# Player_Module.net
KiCad netlist of a schematic drawn in EAGLE
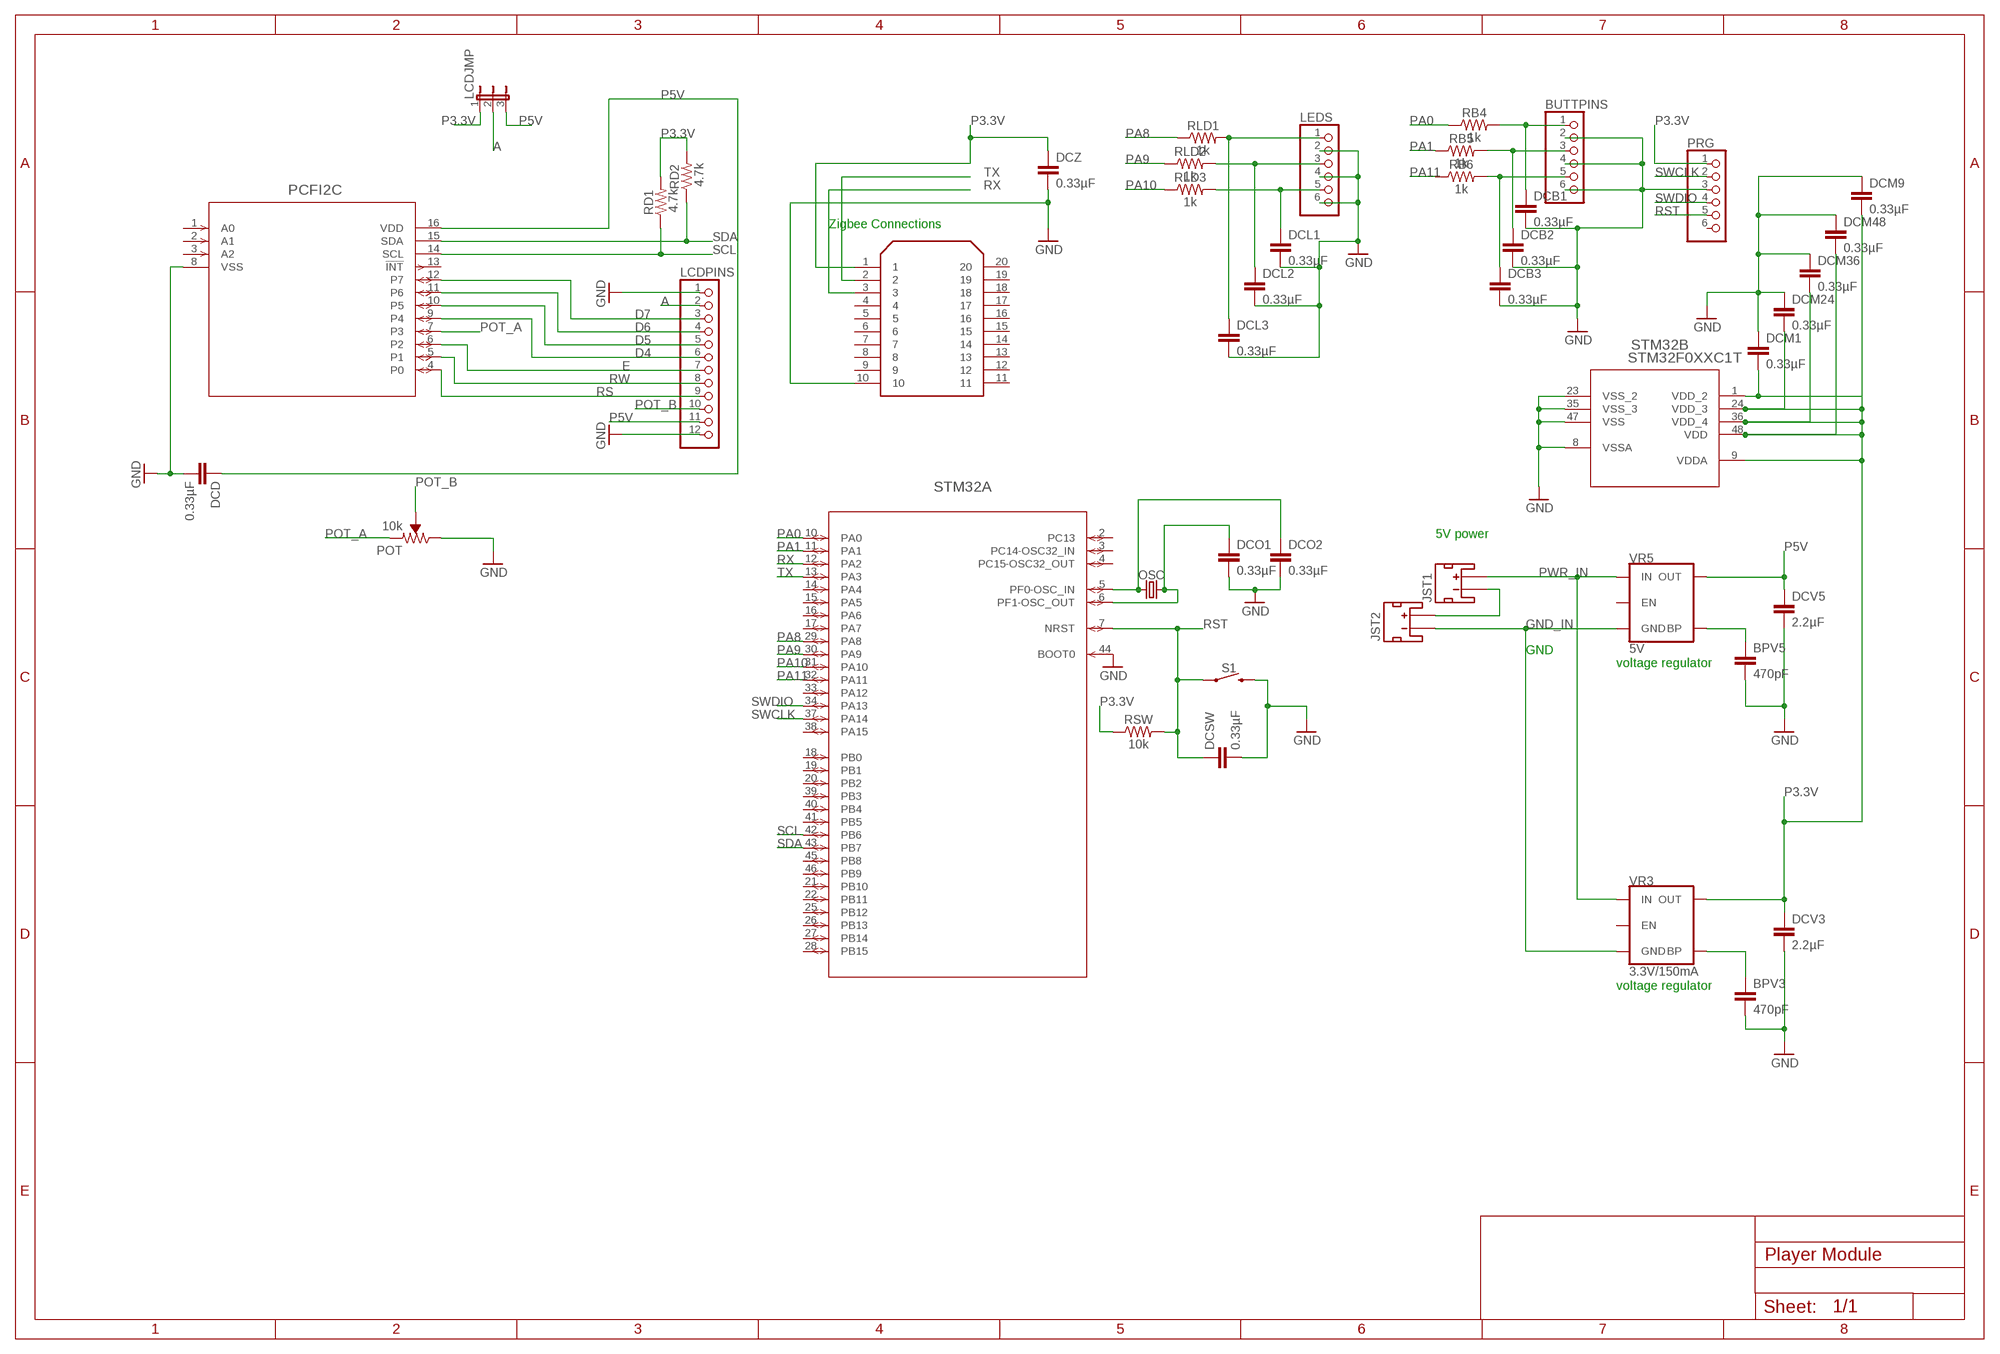
[diagram p0: schematic, sheet 1]

(export (version "E")
  (design (tool "Eeschema 10.0.6"))
  (components
    (comp (ref "BPV3")
      (value "470pF")
      (footprint "eagle-import:0805")
      (libsource (lib "eagle-import") (part "0.33UF/330NF-0805-50V-10%"))
    )
    (comp (ref "BPV5")
      (value "470pF")
      (footprint "eagle-import:0805")
      (libsource (lib "eagle-import") (part "0.33UF/330NF-0805-50V-10%"))
    )
    (comp (ref "BUTTPINS")
      (value "PINHD-1X6")
      (footprint "eagle-import:1X06")
      (libsource (lib "eagle-import") (part "PINHD-1X6"))
    )
    (comp (ref "DCB1")
      (value "0.33µF")
      (footprint "eagle-import:0805")
      (libsource (lib "eagle-import") (part "0.33UF/330NF-0805-50V-10%"))
    )
    (comp (ref "DCB2")
      (value "0.33µF")
      (footprint "eagle-import:0805")
      (libsource (lib "eagle-import") (part "0.33UF/330NF-0805-50V-10%"))
    )
    (comp (ref "DCB3")
      (value "0.33µF")
      (footprint "eagle-import:0805")
      (libsource (lib "eagle-import") (part "0.33UF/330NF-0805-50V-10%"))
    )
    (comp (ref "DCD")
      (value "0.33µF")
      (footprint "eagle-import:0805")
      (libsource (lib "eagle-import") (part "0.33UF/330NF-0805-50V-10%"))
    )
    (comp (ref "DCL1")
      (value "0.33µF")
      (footprint "eagle-import:0805")
      (libsource (lib "eagle-import") (part "0.33UF/330NF-0805-50V-10%"))
    )
    (comp (ref "DCL2")
      (value "0.33µF")
      (footprint "eagle-import:0805")
      (libsource (lib "eagle-import") (part "0.33UF/330NF-0805-50V-10%"))
    )
    (comp (ref "DCL3")
      (value "0.33µF")
      (footprint "eagle-import:0805")
      (libsource (lib "eagle-import") (part "0.33UF/330NF-0805-50V-10%"))
    )
    (comp (ref "DCM1")
      (value "0.33µF")
      (footprint "eagle-import:0805")
      (libsource (lib "eagle-import") (part "0.33UF/330NF-0805-50V-10%"))
    )
    (comp (ref "DCM9")
      (value "0.33µF")
      (footprint "eagle-import:0805")
      (libsource (lib "eagle-import") (part "0.33UF/330NF-0805-50V-10%"))
    )
    (comp (ref "DCM24")
      (value "0.33µF")
      (footprint "eagle-import:0805")
      (libsource (lib "eagle-import") (part "0.33UF/330NF-0805-50V-10%"))
    )
    (comp (ref "DCM36")
      (value "0.33µF")
      (footprint "eagle-import:0805")
      (libsource (lib "eagle-import") (part "0.33UF/330NF-0805-50V-10%"))
    )
    (comp (ref "DCM48")
      (value "0.33µF")
      (footprint "eagle-import:0805")
      (libsource (lib "eagle-import") (part "0.33UF/330NF-0805-50V-10%"))
    )
    (comp (ref "DCO1")
      (value "0.33µF")
      (footprint "eagle-import:0805")
      (libsource (lib "eagle-import") (part "0.33UF/330NF-0805-50V-10%"))
    )
    (comp (ref "DCO2")
      (value "0.33µF")
      (footprint "eagle-import:0805")
      (libsource (lib "eagle-import") (part "0.33UF/330NF-0805-50V-10%"))
    )
    (comp (ref "DCSW")
      (value "0.33µF")
      (footprint "eagle-import:0805")
      (libsource (lib "eagle-import") (part "0.33UF/330NF-0805-50V-10%"))
    )
    (comp (ref "DCV3")
      (value "2.2µF")
      (footprint "eagle-import:0805")
      (libsource (lib "eagle-import") (part "0.33UF/330NF-0805-50V-10%"))
    )
    (comp (ref "DCV5")
      (value "2.2µF")
      (footprint "eagle-import:0805")
      (libsource (lib "eagle-import") (part "0.33UF/330NF-0805-50V-10%"))
    )
    (comp (ref "DCZ")
      (value "0.33µF")
      (footprint "eagle-import:0805")
      (libsource (lib "eagle-import") (part "0.33UF/330NF-0805-50V-10%"))
    )
    (comp (ref "JST1")
      (value "JST_2MM_MALE")
      (footprint "eagle-import:JST-2-SMD")
      (libsource (lib "eagle-import") (part "JST_2MM_MALE"))
    )
    (comp (ref "JST2")
      (value "JST_2MM_MALE")
      (footprint "eagle-import:JST-2-SMD")
      (libsource (lib "eagle-import") (part "JST_2MM_MALE"))
    )
    (comp (ref "LCDJMP")
      (value "JP2E")
      (footprint "eagle-import:JP2")
      (libsource (lib "eagle-import") (part "JP2E"))
    )
    (comp (ref "LCDPINS")
      (value "PINHD-1X12")
      (footprint "eagle-import:1X12")
      (libsource (lib "eagle-import") (part "PINHD-1X12"))
    )
    (comp (ref "LEDS")
      (value "PINHD-1X6")
      (footprint "eagle-import:1X06")
      (libsource (lib "eagle-import") (part "PINHD-1X6"))
    )
    (comp (ref "OSC")
      (value "CRYSTALPTH-HC49US")
      (footprint "eagle-import:HC49US")
      (libsource (lib "eagle-import") (part "CRYSTALPTH-HC49US"))
    )
    (comp (ref "PCFI2C")
      (value "PCF8574T/3,512SOT162-1-M")
      (footprint "eagle-import:SOT162-1-M")
      (fields (field (name "MANUFACTURER_PART_NUMBER") "PCF8574T3512"))
      (libsource (lib "eagle-import") (part "PCF8574T/3,512SOT162-1-M"))
    )
    (comp (ref "POT")
      (value "10k")
      (footprint "eagle-import:TRIMPOT-PTH-3386U")
      (libsource (lib "eagle-import") (part "TRIMPOT-PTH-10MM-KNOB-1/2W-10%"))
    )
    (comp (ref "PRG")
      (value "PINHD-1X6")
      (footprint "eagle-import:1X06")
      (libsource (lib "eagle-import") (part "PINHD-1X6"))
    )
    (comp (ref "RB4")
      (value "1k")
      (footprint "eagle-import:0805")
      (libsource (lib "eagle-import") (part "RESISTOR0805"))
    )
    (comp (ref "RB5")
      (value "1k")
      (footprint "eagle-import:0805")
      (libsource (lib "eagle-import") (part "RESISTOR0805"))
    )
    (comp (ref "RB6")
      (value "1k")
      (footprint "eagle-import:0805")
      (libsource (lib "eagle-import") (part "RESISTOR0805"))
    )
    (comp (ref "RD1")
      (value "4.7k")
      (footprint "eagle-import:0805")
      (libsource (lib "eagle-import") (part "RESISTOR0805"))
    )
    (comp (ref "RD2")
      (value "4.7k")
      (footprint "eagle-import:0805")
      (libsource (lib "eagle-import") (part "RESISTOR0805"))
    )
    (comp (ref "RLD1")
      (value "1k")
      (footprint "eagle-import:0805")
      (libsource (lib "eagle-import") (part "RESISTOR0805"))
    )
    (comp (ref "RLD2")
      (value "1k")
      (footprint "eagle-import:0805")
      (libsource (lib "eagle-import") (part "RESISTOR0805"))
    )
    (comp (ref "RLD3")
      (value "1k")
      (footprint "eagle-import:0805")
      (libsource (lib "eagle-import") (part "RESISTOR0805"))
    )
    (comp (ref "RSW")
      (value "10k")
      (footprint "eagle-import:0805")
      (libsource (lib "eagle-import") (part "RESISTOR0805"))
    )
    (comp (ref "S1")
      (value "MOMENTARY-SWITCH-SPST-SMD-5.2MM")
      (footprint "eagle-import:TACTILE_SWITCH_SMD_5.2MM")
      (libsource (lib "eagle-import") (part "MOMENTARY-SWITCH-SPST-SMD-5.2MM"))
    )
    (comp (ref "STM32")
      (value "STM32F0XXC1T")
      (footprint "eagle-import:LQFP48-7X7MM")
      (fields (field (name "MANUFACTURER_PART_NUMBER") "stm32f0xxc1t"))
      (libsource (lib "eagle-import") (part "STM32F0XXC1T"))
    )
    (comp (ref "VR3")
      (value "3.3V/150mA")
      (footprint "eagle-import:SOT23-5")
      (libsource (lib "eagle-import") (part "V_REG_MIC52053.3V"))
    )
    (comp (ref "VR5")
      (value "5V")
      (footprint "eagle-import:SOT23-5")
      (libsource (lib "eagle-import") (part "V_REG_MIC52055V"))
    )
    (comp (ref "XBEE")
      (value "XB24-BPIT-004")
      (footprint "eagle-import:DIP-20")
      (fields (field (name "MF") "Digi International"))
      (libsource (lib "eagle-import") (part "XB24-BPIT-004"))
    )
  )
  (nets
    (net (code "1") (name "/A") (class "Default")
      (node (ref "LCDJMP") (pin "2") (pinfunction "2_2") (pintype "passive"))
      (node (ref "LCDPINS") (pin "2") (pinfunction "2_2") (pintype "passive"))
    )
    (net (code "2") (name "/D4") (class "Default")
      (node (ref "LCDPINS") (pin "6") (pinfunction "6_6") (pintype "passive"))
      (node (ref "PCFI2C") (pin "9") (pinfunction "P4_9") (pintype "bidirectional"))
    )
    (net (code "3") (name "/D5") (class "Default")
      (node (ref "LCDPINS") (pin "5") (pinfunction "5_5") (pintype "passive"))
      (node (ref "PCFI2C") (pin "10") (pinfunction "P5_10") (pintype "bidirectional"))
    )
    (net (code "4") (name "/D6") (class "Default")
      (node (ref "LCDPINS") (pin "4") (pinfunction "4_4") (pintype "passive"))
      (node (ref "PCFI2C") (pin "11") (pinfunction "P6_11") (pintype "bidirectional"))
    )
    (net (code "5") (name "/D7") (class "Default")
      (node (ref "LCDPINS") (pin "3") (pinfunction "3_3") (pintype "passive"))
      (node (ref "PCFI2C") (pin "12") (pinfunction "P7_12") (pintype "bidirectional"))
    )
    (net (code "6") (name "/E") (class "Default")
      (node (ref "LCDPINS") (pin "7") (pinfunction "7_7") (pintype "passive"))
      (node (ref "PCFI2C") (pin "6") (pinfunction "P2_6") (pintype "bidirectional"))
    )
    (net (code "7") (name "/GND_IN") (class "Default")
      (node (ref "JST2") (pin "1") (pinfunction "-_1") (pintype "bidirectional"))
      (node (ref "VR3") (pin "2") (pinfunction "GND_2") (pintype "input"))
      (node (ref "VR5") (pin "2") (pinfunction "GND_2") (pintype "input"))
    )
    (net (code "8") (name "/P3.3V") (class "Default")
      (node (ref "DCM1") (pin "2") (pinfunction "2_2") (pintype "passive"))
      (node (ref "DCM24") (pin "2") (pinfunction "2_2") (pintype "passive"))
      (node (ref "DCM36") (pin "2") (pinfunction "2_2") (pintype "passive"))
      (node (ref "DCM48") (pin "2") (pinfunction "2_2") (pintype "passive"))
      (node (ref "DCM9") (pin "2") (pinfunction "2_2") (pintype "passive"))
      (node (ref "DCV3") (pin "1") (pinfunction "1_1") (pintype "passive"))
      (node (ref "DCZ") (pin "1") (pinfunction "1_1") (pintype "passive"))
      (node (ref "LCDJMP") (pin "1") (pinfunction "1_1") (pintype "passive"))
      (node (ref "PRG") (pin "1") (pinfunction "1_1") (pintype "passive"))
      (node (ref "RD1") (pin "2") (pinfunction "2_2") (pintype "passive"))
      (node (ref "RD2") (pin "2") (pinfunction "2_2") (pintype "passive"))
      (node (ref "RSW") (pin "1") (pinfunction "1_1") (pintype "passive"))
      (node (ref "STM32") (pin "1") (pinfunction "VDD_2_1") (pintype "power_in"))
      (node (ref "STM32") (pin "24") (pinfunction "VDD_3_24") (pintype "power_in"))
      (node (ref "STM32") (pin "36") (pinfunction "VDD_4_36") (pintype "power_in"))
      (node (ref "STM32") (pin "48") (pinfunction "VDD_48") (pintype "power_in"))
      (node (ref "STM32") (pin "9") (pinfunction "VDDA_9") (pintype "power_in"))
      (node (ref "VR3") (pin "5") (pinfunction "OUT_5") (pintype "passive"))
      (node (ref "XBEE") (pin "1") (pinfunction "1_1") (pintype "bidirectional"))
    )
    (net (code "9") (name "/P5V") (class "Default")
      (node (ref "DCD") (pin "1") (pinfunction "1_1") (pintype "passive"))
      (node (ref "DCV5") (pin "1") (pinfunction "1_1") (pintype "passive"))
      (node (ref "LCDJMP") (pin "3") (pinfunction "3_3") (pintype "passive"))
      (node (ref "LCDPINS") (pin "11") (pinfunction "11_11") (pintype "passive"))
      (node (ref "PCFI2C") (pin "16") (pinfunction "VDD_16") (pintype "power_in"))
      (node (ref "VR5") (pin "5") (pinfunction "OUT_5") (pintype "passive"))
    )
    (net (code "10") (name "/PA0") (class "Default")
      (node (ref "RB4") (pin "1") (pinfunction "1_1") (pintype "passive"))
      (node (ref "STM32") (pin "10") (pinfunction "PA0_10") (pintype "bidirectional"))
    )
    (net (code "11") (name "/PA1") (class "Default")
      (node (ref "RB5") (pin "1") (pinfunction "1_1") (pintype "passive"))
      (node (ref "STM32") (pin "11") (pinfunction "PA1_11") (pintype "bidirectional"))
    )
    (net (code "12") (name "/PA8") (class "Default")
      (node (ref "RLD1") (pin "1") (pinfunction "1_1") (pintype "passive"))
      (node (ref "STM32") (pin "29") (pinfunction "PA8_29") (pintype "bidirectional"))
    )
    (net (code "13") (name "/PA9") (class "Default")
      (node (ref "RLD2") (pin "1") (pinfunction "1_1") (pintype "passive"))
      (node (ref "STM32") (pin "30") (pinfunction "PA9_30") (pintype "bidirectional"))
    )
    (net (code "14") (name "/PA10") (class "Default")
      (node (ref "RLD3") (pin "1") (pinfunction "1_1") (pintype "passive"))
      (node (ref "STM32") (pin "31") (pinfunction "PA10_31") (pintype "bidirectional"))
    )
    (net (code "15") (name "/PA11") (class "Default")
      (node (ref "RB6") (pin "1") (pinfunction "1_1") (pintype "passive"))
      (node (ref "STM32") (pin "32") (pinfunction "PA11_32") (pintype "bidirectional"))
    )
    (net (code "16") (name "/POT_A") (class "Default")
      (node (ref "PCFI2C") (pin "7") (pinfunction "P3_7") (pintype "bidirectional"))
      (node (ref "POT") (pin "1") (pinfunction "CCW_1") (pintype "passive"))
    )
    (net (code "17") (name "/POT_B") (class "Default")
      (node (ref "LCDPINS") (pin "10") (pinfunction "10_10") (pintype "passive"))
      (node (ref "POT") (pin "2") (pinfunction "WIPER_2") (pintype "passive"))
    )
    (net (code "18") (name "/PWR_IN") (class "Default")
      (node (ref "JST1") (pin "2") (pinfunction "+_2") (pintype "bidirectional"))
      (node (ref "VR3") (pin "1") (pinfunction "IN_1") (pintype "input"))
      (node (ref "VR5") (pin "1") (pinfunction "IN_1") (pintype "input"))
    )
    (net (code "19") (name "/RS") (class "Default")
      (node (ref "LCDPINS") (pin "9") (pinfunction "9_9") (pintype "passive"))
      (node (ref "PCFI2C") (pin "4") (pinfunction "P0_4") (pintype "bidirectional"))
    )
    (net (code "20") (name "/RST") (class "Default")
      (node (ref "DCSW") (pin "1") (pinfunction "1_1") (pintype "passive"))
      (node (ref "PRG") (pin "5") (pinfunction "5_5") (pintype "passive"))
      (node (ref "RSW") (pin "2") (pinfunction "2_2") (pintype "passive"))
      (node (ref "S1") (pin "1") (pinfunction "1_1") (pintype "passive"))
      (node (ref "STM32") (pin "7") (pinfunction "NRST_7") (pintype "bidirectional"))
    )
    (net (code "21") (name "/RW") (class "Default")
      (node (ref "LCDPINS") (pin "8") (pinfunction "8_8") (pintype "passive"))
      (node (ref "PCFI2C") (pin "5") (pinfunction "P1_5") (pintype "bidirectional"))
    )
    (net (code "22") (name "/RX") (class "Default")
      (node (ref "STM32") (pin "12") (pinfunction "PA2_12") (pintype "bidirectional"))
      (node (ref "XBEE") (pin "3") (pinfunction "3_3") (pintype "bidirectional"))
    )
    (net (code "23") (name "/SCL") (class "Default")
      (node (ref "PCFI2C") (pin "14") (pinfunction "SCL_14") (pintype "passive"))
      (node (ref "RD1") (pin "1") (pinfunction "1_1") (pintype "passive"))
      (node (ref "STM32") (pin "42") (pinfunction "PB6_42") (pintype "bidirectional"))
    )
    (net (code "24") (name "/SDA") (class "Default")
      (node (ref "PCFI2C") (pin "15") (pinfunction "SDA_15") (pintype "passive"))
      (node (ref "RD2") (pin "1") (pinfunction "1_1") (pintype "passive"))
      (node (ref "STM32") (pin "43") (pinfunction "PB7_43") (pintype "bidirectional"))
    )
    (net (code "25") (name "/SWCLK") (class "Default")
      (node (ref "PRG") (pin "2") (pinfunction "2_2") (pintype "passive"))
      (node (ref "STM32") (pin "37") (pinfunction "PA14_37") (pintype "bidirectional"))
    )
    (net (code "26") (name "/SWDIO") (class "Default")
      (node (ref "PRG") (pin "4") (pinfunction "4_4") (pintype "passive"))
      (node (ref "STM32") (pin "34") (pinfunction "PA13_34") (pintype "bidirectional"))
    )
    (net (code "27") (name "/TX") (class "Default")
      (node (ref "STM32") (pin "13") (pinfunction "PA3_13") (pintype "bidirectional"))
      (node (ref "XBEE") (pin "2") (pinfunction "2_2") (pintype "bidirectional"))
    )
    (net (code "28") (name "GND") (class "Default")
      (node (ref "BPV3") (pin "2") (pinfunction "2_2") (pintype "passive"))
      (node (ref "BPV5") (pin "2") (pinfunction "2_2") (pintype "passive"))
      (node (ref "BUTTPINS") (pin "2") (pinfunction "2_2") (pintype "passive"))
      (node (ref "BUTTPINS") (pin "4") (pinfunction "4_4") (pintype "passive"))
      (node (ref "BUTTPINS") (pin "6") (pinfunction "6_6") (pintype "passive"))
      (node (ref "DCB1") (pin "2") (pinfunction "2_2") (pintype "passive"))
      (node (ref "DCB2") (pin "2") (pinfunction "2_2") (pintype "passive"))
      (node (ref "DCB3") (pin "2") (pinfunction "2_2") (pintype "passive"))
      (node (ref "DCD") (pin "2") (pinfunction "2_2") (pintype "passive"))
      (node (ref "DCL1") (pin "2") (pinfunction "2_2") (pintype "passive"))
      (node (ref "DCL2") (pin "2") (pinfunction "2_2") (pintype "passive"))
      (node (ref "DCL3") (pin "2") (pinfunction "2_2") (pintype "passive"))
      (node (ref "DCM1") (pin "1") (pinfunction "1_1") (pintype "passive"))
      (node (ref "DCM24") (pin "1") (pinfunction "1_1") (pintype "passive"))
      (node (ref "DCM36") (pin "1") (pinfunction "1_1") (pintype "passive"))
      (node (ref "DCM48") (pin "1") (pinfunction "1_1") (pintype "passive"))
      (node (ref "DCM9") (pin "1") (pinfunction "1_1") (pintype "passive"))
      (node (ref "DCO1") (pin "2") (pinfunction "2_2") (pintype "passive"))
      (node (ref "DCO2") (pin "2") (pinfunction "2_2") (pintype "passive"))
      (node (ref "DCSW") (pin "2") (pinfunction "2_2") (pintype "passive"))
      (node (ref "DCV3") (pin "2") (pinfunction "2_2") (pintype "passive"))
      (node (ref "DCV5") (pin "2") (pinfunction "2_2") (pintype "passive"))
      (node (ref "DCZ") (pin "2") (pinfunction "2_2") (pintype "passive"))
      (node (ref "LCDPINS") (pin "1") (pinfunction "1_1") (pintype "passive"))
      (node (ref "LCDPINS") (pin "12") (pinfunction "12_12") (pintype "passive"))
      (node (ref "LEDS") (pin "2") (pinfunction "2_2") (pintype "passive"))
      (node (ref "LEDS") (pin "4") (pinfunction "4_4") (pintype "passive"))
      (node (ref "LEDS") (pin "6") (pinfunction "6_6") (pintype "passive"))
      (node (ref "PCFI2C") (pin "8") (pinfunction "VSS_8") (pintype "power_in"))
      (node (ref "POT") (pin "3") (pinfunction "CW_3") (pintype "passive"))
      (node (ref "PRG") (pin "3") (pinfunction "3_3") (pintype "passive"))
      (node (ref "S1") (pin "3") (pinfunction "2_3") (pintype "passive"))
      (node (ref "STM32") (pin "23") (pinfunction "VSS_2_23") (pintype "power_in"))
      (node (ref "STM32") (pin "35") (pinfunction "VSS_3_35") (pintype "power_in"))
      (node (ref "STM32") (pin "44") (pinfunction "BOOT0_44") (pintype "input"))
      (node (ref "STM32") (pin "47") (pinfunction "VSS_47") (pintype "power_in"))
      (node (ref "STM32") (pin "8") (pinfunction "VSSA_8") (pintype "power_in"))
      (node (ref "XBEE") (pin "10") (pinfunction "10_10") (pintype "bidirectional"))
    )
    (net (code "29") (name "Net-(BUTTPINS-Pad1)") (class "Default")
      (node (ref "BUTTPINS") (pin "1") (pinfunction "1_1") (pintype "passive"))
      (node (ref "DCB1") (pin "1") (pinfunction "1_1") (pintype "passive"))
      (node (ref "RB4") (pin "2") (pinfunction "2_2") (pintype "passive"))
    )
    (net (code "30") (name "Net-(BUTTPINS-Pad3)") (class "Default")
      (node (ref "BUTTPINS") (pin "3") (pinfunction "3_3") (pintype "passive"))
      (node (ref "DCB2") (pin "1") (pinfunction "1_1") (pintype "passive"))
      (node (ref "RB5") (pin "2") (pinfunction "2_2") (pintype "passive"))
    )
    (net (code "31") (name "Net-(BUTTPINS-Pad5)") (class "Default")
      (node (ref "BUTTPINS") (pin "5") (pinfunction "5_5") (pintype "passive"))
      (node (ref "DCB3") (pin "1") (pinfunction "1_1") (pintype "passive"))
      (node (ref "RB6") (pin "2") (pinfunction "2_2") (pintype "passive"))
    )
    (net (code "32") (name "Net-(DCL1-Pad1)") (class "Default")
      (node (ref "DCL1") (pin "1") (pinfunction "1_1") (pintype "passive"))
      (node (ref "LEDS") (pin "5") (pinfunction "5_5") (pintype "passive"))
      (node (ref "RLD3") (pin "2") (pinfunction "2_2") (pintype "passive"))
    )
    (net (code "33") (name "Net-(DCL2-Pad1)") (class "Default")
      (node (ref "DCL2") (pin "1") (pinfunction "1_1") (pintype "passive"))
      (node (ref "LEDS") (pin "3") (pinfunction "3_3") (pintype "passive"))
      (node (ref "RLD2") (pin "2") (pinfunction "2_2") (pintype "passive"))
    )
    (net (code "34") (name "Net-(DCL3-Pad1)") (class "Default")
      (node (ref "DCL3") (pin "1") (pinfunction "1_1") (pintype "passive"))
      (node (ref "LEDS") (pin "1") (pinfunction "1_1") (pintype "passive"))
      (node (ref "RLD1") (pin "2") (pinfunction "2_2") (pintype "passive"))
    )
    (net (code "35") (name "Net-(JST1--)") (class "Default")
      (node (ref "JST1") (pin "1") (pinfunction "-_1") (pintype "bidirectional"))
      (node (ref "JST2") (pin "2") (pinfunction "+_2") (pintype "bidirectional"))
    )
    (net (code "36") (name "Net-(STM32A-PF0-OSC_IN)") (class "Default")
      (node (ref "DCO2") (pin "1") (pinfunction "1_1") (pintype "passive"))
      (node (ref "OSC") (pin "1") (pinfunction "1_1") (pintype "passive"))
      (node (ref "STM32") (pin "5") (pinfunction "PF0-OSC_IN_5") (pintype "bidirectional"))
    )
    (net (code "37") (name "Net-(STM32A-PF1-OSC_OUT)") (class "Default")
      (node (ref "DCO1") (pin "1") (pinfunction "1_1") (pintype "passive"))
      (node (ref "OSC") (pin "2") (pinfunction "2_2") (pintype "passive"))
      (node (ref "STM32") (pin "6") (pinfunction "PF1-OSC_OUT_6") (pintype "bidirectional"))
    )
    (net (code "38") (name "Net-(VR3-BP)") (class "Default")
      (node (ref "BPV3") (pin "1") (pinfunction "1_1") (pintype "passive"))
      (node (ref "VR3") (pin "4") (pinfunction "BP_4") (pintype "input"))
    )
    (net (code "39") (name "Net-(VR5-BP)") (class "Default")
      (node (ref "BPV5") (pin "1") (pinfunction "1_1") (pintype "passive"))
      (node (ref "VR5") (pin "4") (pinfunction "BP_4") (pintype "input"))
    )
    (net (code "40") (name "unconnected-(JST1-PAD1-PadNC1)") (class "Default")
      (node (ref "JST1") (pin "NC1") (pinfunction "PAD1_NC1") (pintype "bidirectional"))
    )
    (net (code "41") (name "unconnected-(JST1-PAD2-PadNC2)") (class "Default")
      (node (ref "JST1") (pin "NC2") (pinfunction "PAD2_NC2") (pintype "bidirectional"))
    )
    (net (code "42") (name "unconnected-(JST2-PAD1-PadNC1)") (class "Default")
      (node (ref "JST2") (pin "NC1") (pinfunction "PAD1_NC1") (pintype "bidirectional"))
    )
    (net (code "43") (name "unconnected-(JST2-PAD2-PadNC2)") (class "Default")
      (node (ref "JST2") (pin "NC2") (pinfunction "PAD2_NC2") (pintype "bidirectional"))
    )
    (net (code "44") (name "unconnected-(PCFI2C-A0-Pad1)") (class "Default")
      (node (ref "PCFI2C") (pin "1") (pinfunction "A0_1") (pintype "input"))
    )
    (net (code "45") (name "unconnected-(PCFI2C-A1-Pad2)") (class "Default")
      (node (ref "PCFI2C") (pin "2") (pinfunction "A1_2") (pintype "input"))
    )
    (net (code "46") (name "unconnected-(PCFI2C-A2-Pad3)") (class "Default")
      (node (ref "PCFI2C") (pin "3") (pinfunction "A2_3") (pintype "input"))
    )
    (net (code "47") (name "unconnected-(PCFI2C-~{INT}-Pad13)") (class "Default")
      (node (ref "PCFI2C") (pin "13") (pinfunction "~{INT}_13") (pintype "output"))
    )
    (net (code "48") (name "unconnected-(PRG-Pad6)") (class "Default")
      (node (ref "PRG") (pin "6") (pinfunction "6_6") (pintype "passive"))
    )
    (net (code "49") (name "unconnected-(STM32A-PA4-Pad14)") (class "Default")
      (node (ref "STM32") (pin "14") (pinfunction "PA4_14") (pintype "bidirectional"))
    )
    (net (code "50") (name "unconnected-(STM32A-PA5-Pad15)") (class "Default")
      (node (ref "STM32") (pin "15") (pinfunction "PA5_15") (pintype "bidirectional"))
    )
    (net (code "51") (name "unconnected-(STM32A-PA6-Pad16)") (class "Default")
      (node (ref "STM32") (pin "16") (pinfunction "PA6_16") (pintype "bidirectional"))
    )
    (net (code "52") (name "unconnected-(STM32A-PA7-Pad17)") (class "Default")
      (node (ref "STM32") (pin "17") (pinfunction "PA7_17") (pintype "bidirectional"))
    )
    (net (code "53") (name "unconnected-(STM32A-PA12-Pad33)") (class "Default")
      (node (ref "STM32") (pin "33") (pinfunction "PA12_33") (pintype "bidirectional"))
    )
    (net (code "54") (name "unconnected-(STM32A-PA15-Pad38)") (class "Default")
      (node (ref "STM32") (pin "38") (pinfunction "PA15_38") (pintype "bidirectional"))
    )
    (net (code "55") (name "unconnected-(STM32A-PB0-Pad18)") (class "Default")
      (node (ref "STM32") (pin "18") (pinfunction "PB0_18") (pintype "bidirectional"))
    )
    (net (code "56") (name "unconnected-(STM32A-PB1-Pad19)") (class "Default")
      (node (ref "STM32") (pin "19") (pinfunction "PB1_19") (pintype "bidirectional"))
    )
    (net (code "57") (name "unconnected-(STM32A-PB2-Pad20)") (class "Default")
      (node (ref "STM32") (pin "20") (pinfunction "PB2_20") (pintype "bidirectional"))
    )
    (net (code "58") (name "unconnected-(STM32A-PB3-Pad39)") (class "Default")
      (node (ref "STM32") (pin "39") (pinfunction "PB3_39") (pintype "bidirectional"))
    )
    (net (code "59") (name "unconnected-(STM32A-PB4-Pad40)") (class "Default")
      (node (ref "STM32") (pin "40") (pinfunction "PB4_40") (pintype "bidirectional"))
    )
    (net (code "60") (name "unconnected-(STM32A-PB5-Pad41)") (class "Default")
      (node (ref "STM32") (pin "41") (pinfunction "PB5_41") (pintype "bidirectional"))
    )
    (net (code "61") (name "unconnected-(STM32A-PB8-Pad45)") (class "Default")
      (node (ref "STM32") (pin "45") (pinfunction "PB8_45") (pintype "bidirectional"))
    )
    (net (code "62") (name "unconnected-(STM32A-PB9-Pad46)") (class "Default")
      (node (ref "STM32") (pin "46") (pinfunction "PB9_46") (pintype "bidirectional"))
    )
    (net (code "63") (name "unconnected-(STM32A-PB10-Pad21)") (class "Default")
      (node (ref "STM32") (pin "21") (pinfunction "PB10_21") (pintype "bidirectional"))
    )
    (net (code "64") (name "unconnected-(STM32A-PB11-Pad22)") (class "Default")
      (node (ref "STM32") (pin "22") (pinfunction "PB11_22") (pintype "bidirectional"))
    )
    (net (code "65") (name "unconnected-(STM32A-PB12-Pad25)") (class "Default")
      (node (ref "STM32") (pin "25") (pinfunction "PB12_25") (pintype "bidirectional"))
    )
    (net (code "66") (name "unconnected-(STM32A-PB13-Pad26)") (class "Default")
      (node (ref "STM32") (pin "26") (pinfunction "PB13_26") (pintype "bidirectional"))
    )
    (net (code "67") (name "unconnected-(STM32A-PB14-Pad27)") (class "Default")
      (node (ref "STM32") (pin "27") (pinfunction "PB14_27") (pintype "bidirectional"))
    )
    (net (code "68") (name "unconnected-(STM32A-PB15-Pad28)") (class "Default")
      (node (ref "STM32") (pin "28") (pinfunction "PB15_28") (pintype "bidirectional"))
    )
    (net (code "69") (name "unconnected-(STM32A-PC13-Pad2)") (class "Default")
      (node (ref "STM32") (pin "2") (pinfunction "PC13_2") (pintype "bidirectional"))
    )
    (net (code "70") (name "unconnected-(STM32A-PC14-OSC32_IN-Pad3)") (class "Default")
      (node (ref "STM32") (pin "3") (pinfunction "PC14-OSC32_IN_3") (pintype "bidirectional"))
    )
    (net (code "71") (name "unconnected-(STM32A-PC15-OSC32_OUT-Pad4)") (class "Default")
      (node (ref "STM32") (pin "4") (pinfunction "PC15-OSC32_OUT_4") (pintype "bidirectional"))
    )
    (net (code "72") (name "unconnected-(VR3-EN-Pad3)") (class "Default")
      (node (ref "VR3") (pin "3") (pinfunction "EN_3") (pintype "input"))
    )
    (net (code "73") (name "unconnected-(VR5-EN-Pad3)") (class "Default")
      (node (ref "VR5") (pin "3") (pinfunction "EN_3") (pintype "input"))
    )
    (net (code "74") (name "unconnected-(XBEE-Pad4)") (class "Default")
      (node (ref "XBEE") (pin "4") (pinfunction "4_4") (pintype "bidirectional"))
    )
    (net (code "75") (name "unconnected-(XBEE-Pad5)") (class "Default")
      (node (ref "XBEE") (pin "5") (pinfunction "5_5") (pintype "bidirectional"))
    )
    (net (code "76") (name "unconnected-(XBEE-Pad6)") (class "Default")
      (node (ref "XBEE") (pin "6") (pinfunction "6_6") (pintype "bidirectional"))
    )
    (net (code "77") (name "unconnected-(XBEE-Pad7)") (class "Default")
      (node (ref "XBEE") (pin "7") (pinfunction "7_7") (pintype "bidirectional"))
    )
    (net (code "78") (name "unconnected-(XBEE-Pad8)") (class "Default")
      (node (ref "XBEE") (pin "8") (pinfunction "8_8") (pintype "bidirectional"))
    )
    (net (code "79") (name "unconnected-(XBEE-Pad9)") (class "Default")
      (node (ref "XBEE") (pin "9") (pinfunction "9_9") (pintype "bidirectional"))
    )
    (net (code "80") (name "unconnected-(XBEE-Pad11)") (class "Default")
      (node (ref "XBEE") (pin "11") (pinfunction "11_11") (pintype "bidirectional"))
    )
    (net (code "81") (name "unconnected-(XBEE-Pad12)") (class "Default")
      (node (ref "XBEE") (pin "12") (pinfunction "12_12") (pintype "bidirectional"))
    )
    (net (code "82") (name "unconnected-(XBEE-Pad13)") (class "Default")
      (node (ref "XBEE") (pin "13") (pinfunction "13_13") (pintype "bidirectional"))
    )
    (net (code "83") (name "unconnected-(XBEE-Pad14)") (class "Default")
      (node (ref "XBEE") (pin "14") (pinfunction "14_14") (pintype "bidirectional"))
    )
    (net (code "84") (name "unconnected-(XBEE-Pad15)") (class "Default")
      (node (ref "XBEE") (pin "15") (pinfunction "15_15") (pintype "bidirectional"))
    )
    (net (code "85") (name "unconnected-(XBEE-Pad16)") (class "Default")
      (node (ref "XBEE") (pin "16") (pinfunction "16_16") (pintype "bidirectional"))
    )
    (net (code "86") (name "unconnected-(XBEE-Pad17)") (class "Default")
      (node (ref "XBEE") (pin "17") (pinfunction "17_17") (pintype "bidirectional"))
    )
    (net (code "87") (name "unconnected-(XBEE-Pad18)") (class "Default")
      (node (ref "XBEE") (pin "18") (pinfunction "18_18") (pintype "bidirectional"))
    )
    (net (code "88") (name "unconnected-(XBEE-Pad19)") (class "Default")
      (node (ref "XBEE") (pin "19") (pinfunction "19_19") (pintype "bidirectional"))
    )
    (net (code "89") (name "unconnected-(XBEE-Pad20)") (class "Default")
      (node (ref "XBEE") (pin "20") (pinfunction "20_20") (pintype "bidirectional"))
    )
  )
)
